# STM32WL_LHCbit.net
KiCad netlist of a schematic drawn in Altium Designer
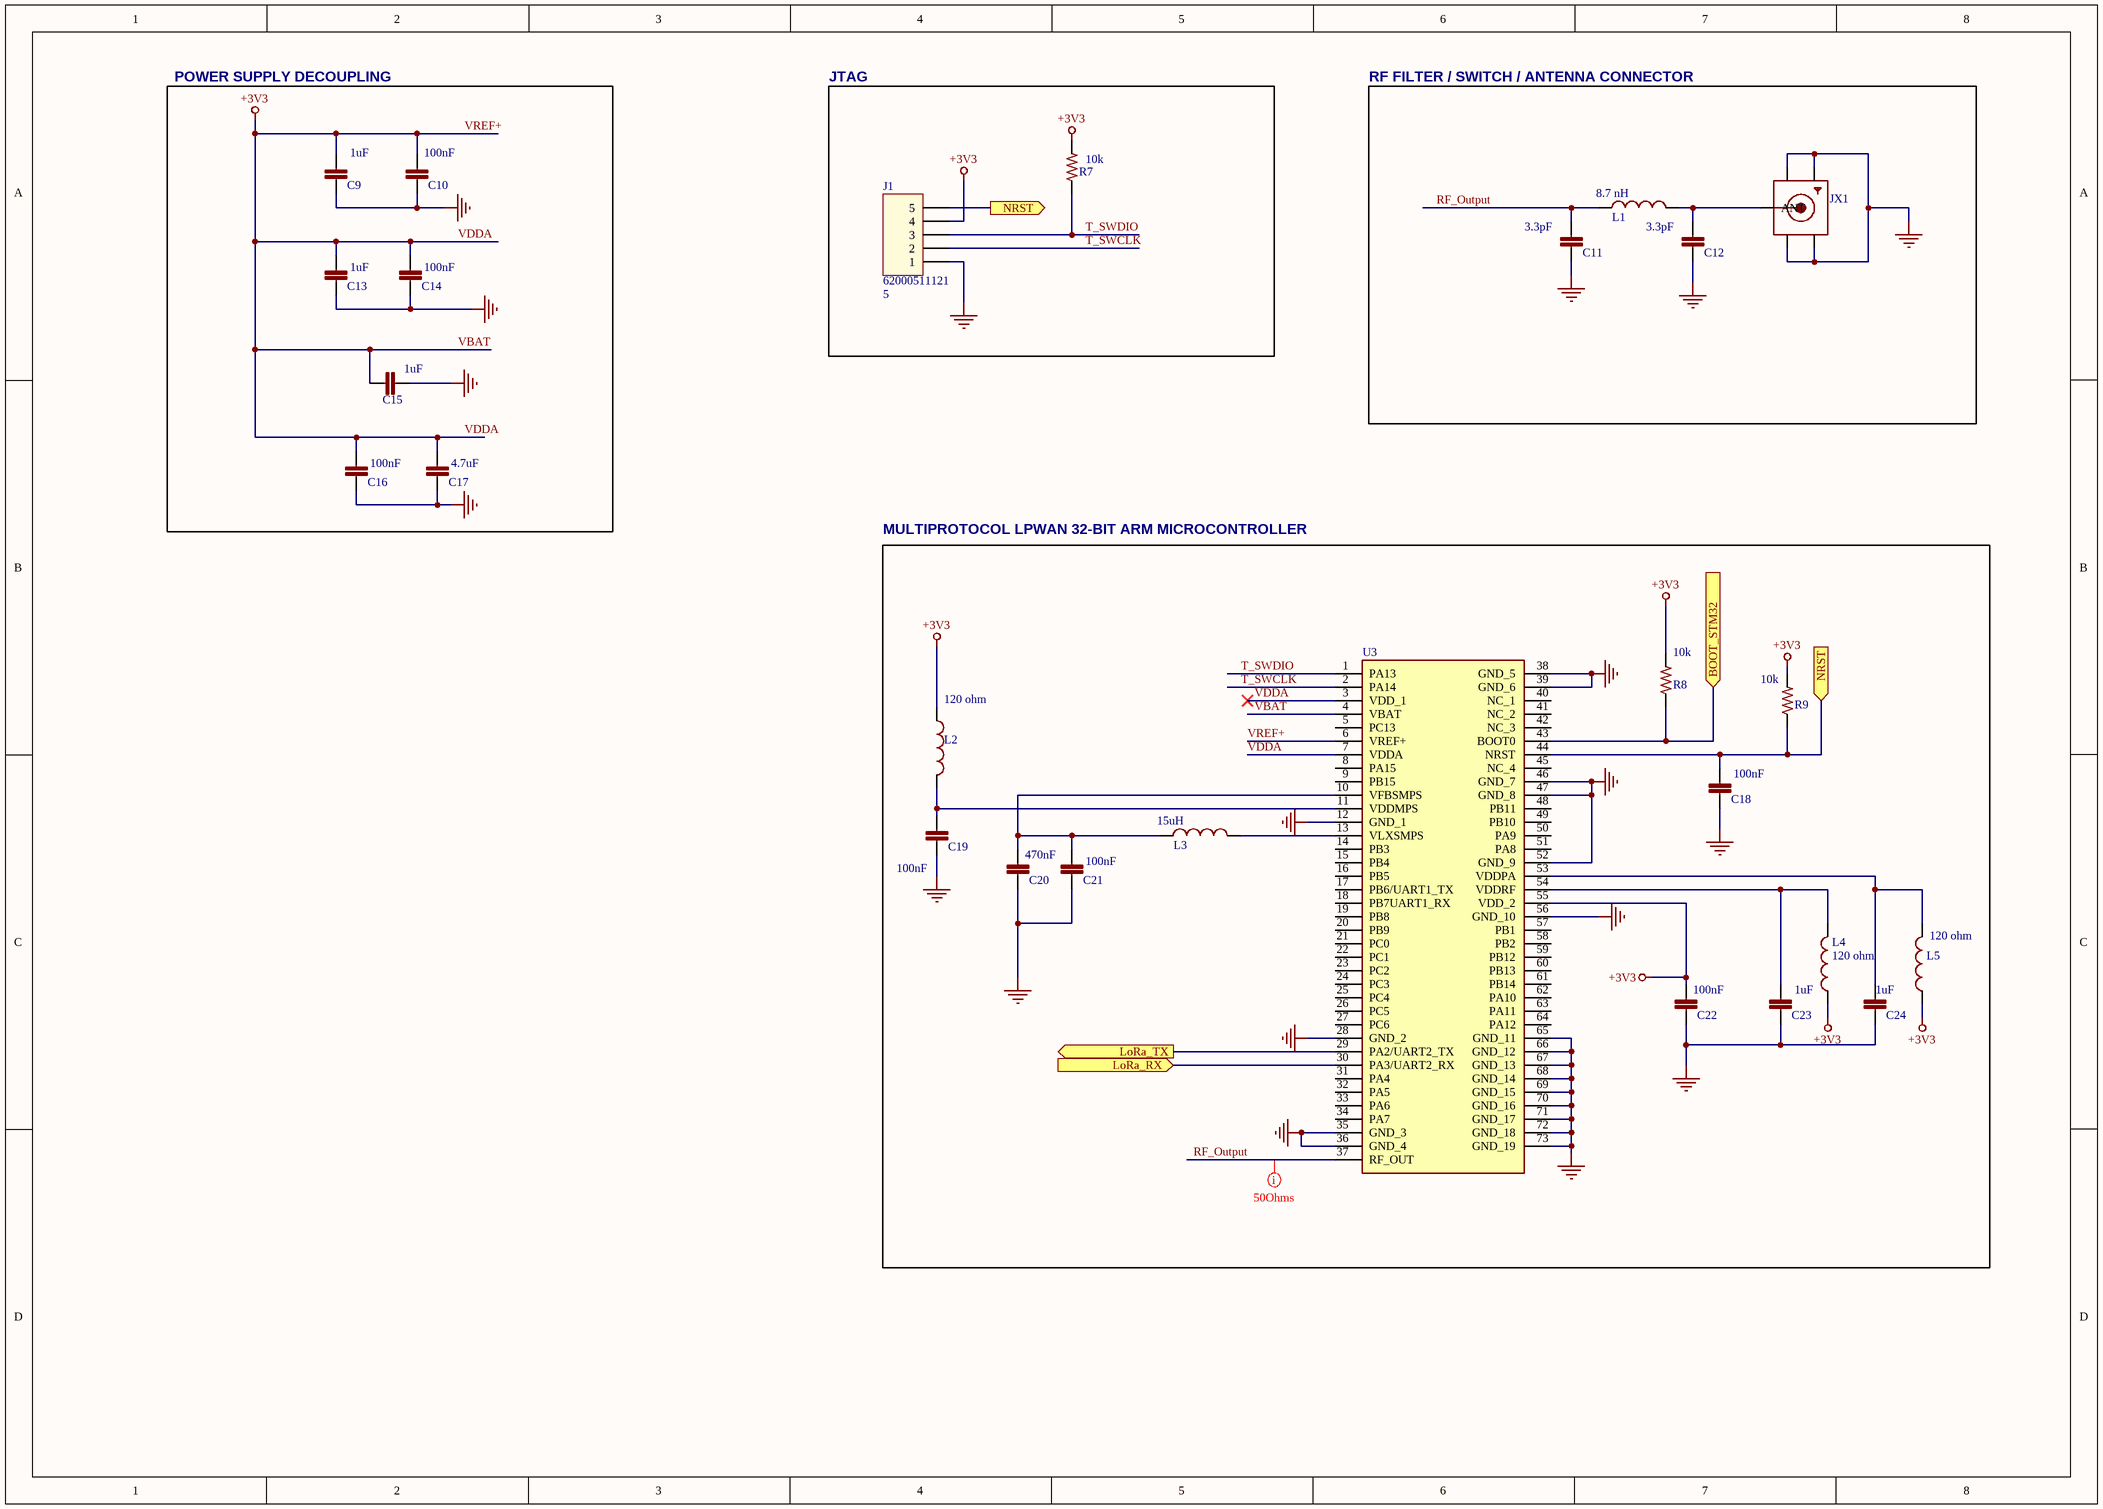
[diagram p0: STM32WL_LHCbit.SchDoc]

(export (version "E")
  (design (tool "Eeschema 10.0.6"))
  (components
    (comp (ref "C9")
      (value "1uF")
      (footprint "C0402")
      (fields (field (name "PART NUMBER") "CL05A105KA5NQNC") (field (name "Comment") "C-EUC0402"))
      (libsource (lib "") (part "C-EUC0402_1"))
    )
    (comp (ref "C10")
      (value "100nF")
      (footprint "C0402")
      (fields (field (name "PART NUMBER") "C0402C104K8") (field (name "Comment") "C-EUC0402"))
      (libsource (lib "") (part "C-EUC0402_1"))
    )
    (comp (ref "C11")
      (value "3.3pF")
      (footprint "C0402")
      (fields (field (name "PART NUMBER") "GRM1555C1H3R3WA01D") (field (name "Comment") "C-EUC0402"))
      (libsource (lib "rcl") (part "C-EUC0402"))
    )
    (comp (ref "C12")
      (value "3.3pF")
      (footprint "C0402")
      (fields (field (name "PART NUMBER") "GRM1555C1H3R3WA01D") (field (name "Comment") "C-EUC0402"))
      (libsource (lib "rcl") (part "C-EUC0402"))
    )
    (comp (ref "C13")
      (value "1uF")
      (footprint "C0402")
      (fields (field (name "PART NUMBER") "CL05A105KA5NQNC") (field (name "Comment") "C-EUC0402"))
      (libsource (lib "") (part "C-EUC0402_1"))
    )
    (comp (ref "C14")
      (value "100nF")
      (footprint "C0402")
      (fields (field (name "PART NUMBER") "C0402C104K8") (field (name "Comment") "C-EUC0402"))
      (libsource (lib "") (part "C-EUC0402_1"))
    )
    (comp (ref "C15")
      (value "1uF")
      (footprint "C0402")
      (fields (field (name "PART NUMBER") "CL05A105KA5NQNC") (field (name "Comment") "C-EUC0402"))
      (libsource (lib "") (part "C-EUC0402_2"))
    )
    (comp (ref "C16")
      (value "100nF")
      (footprint "C0402")
      (fields (field (name "PART NUMBER") "C0402C104K8") (field (name "Comment") "C-EUC0402"))
      (libsource (lib "") (part "C-EUC0402_1"))
    )
    (comp (ref "C17")
      (value "4.7uF")
      (footprint "C0402")
      (fields (field (name "PART NUMBER") "CL05A475MQ5NRNC") (field (name "Comment") "C-EUC0402"))
      (libsource (lib "") (part "C-EUC0402_1"))
    )
    (comp (ref "C18")
      (value "100nF")
      (footprint "C0402")
      (fields (field (name "PART NUMBER") "C0402C104K8") (field (name "Comment") "C-EUC0402"))
      (libsource (lib "") (part "C-EUC0402_1"))
    )
    (comp (ref "C19")
      (value "100nF")
      (footprint "C0402")
      (fields (field (name "PART NUMBER") "C0402C104K8") (field (name "Comment") "C-EUC0402"))
      (libsource (lib "") (part "C-EUC0402_1"))
    )
    (comp (ref "C20")
      (value "470nF")
      (footprint "C0402")
      (fields (field (name "PART NUMBER") "GRM155R61H474KE11D") (field (name "Comment") "C-EUC0402"))
      (libsource (lib "") (part "C-EUC0402_1"))
    )
    (comp (ref "C21")
      (value "100nF")
      (footprint "C0402")
      (fields (field (name "PART NUMBER") "C0402C104K8") (field (name "Comment") "C-EUC0402"))
      (libsource (lib "") (part "C-EUC0402_1"))
    )
    (comp (ref "C22")
      (value "100nF")
      (footprint "C0402")
      (fields (field (name "PART NUMBER") "C0402C104K8") (field (name "Comment") "C-EUC0402"))
      (libsource (lib "") (part "C-EUC0402_1"))
    )
    (comp (ref "C23")
      (value "1uF")
      (footprint "C0402")
      (fields (field (name "PART NUMBER") "CL05A105KA5NQNC") (field (name "Comment") "C-EUC0402"))
      (libsource (lib "") (part "C-EUC0402_1"))
    )
    (comp (ref "C24")
      (value "1uF")
      (footprint "C0402")
      (fields (field (name "PART NUMBER") "CL05A105KA5NQNC") (field (name "Comment") "C-EUC0402"))
      (libsource (lib "") (part "C-EUC0402_1"))
    )
    (comp (ref "J1")
      (value "62000511121")
      (footprint "62000511121")
      (description "WR-PHD 2.00 mm THT Pin Header, 6p")
      (fields (field (name "ALTIUM_VALUE") "5"))
      (libsource (lib "Male_header_200mm") (part "62000511121"))
    )
    (comp (ref "JX1")
      (value "SMACONNECTOR_EDGE_UFL")
      (footprint "SMA_EDGELAUNCH_UFL")
      (fields (field (name "PART NUMBER") "SMA-J-P-H-ST-EM1"))
      (libsource (lib "TE") (part "SMACONNECTOR_EDGE_UFL"))
    )
    (comp (ref "L1")
      (value "8.7 nH")
      (footprint "L0402 - rounded")
      (fields (field (name "PART NUMBER") "LQW15AN8N7G00D") (field (name "Comment") "Ferrite bead 0402"))
      (libsource (lib "rcl") (part "L-US0402"))
    )
    (comp (ref "L2")
      (value "120 ohm")
      (footprint "L0603")
      (fields (field (name "PART NUMBER") "YI160808U121-2R5T") (field (name "Comment") "Ferrite bead 0603"))
      (libsource (lib "rcl") (part "L-US0603"))
    )
    (comp (ref "L3")
      (value "15uH")
      (footprint "L0805")
      (fields (field (name "PART NUMBER") "MLZ2012M150WTD25"))
      (libsource (lib "rcl") (part "L-US0805"))
    )
    (comp (ref "L4")
      (value "120 ohm")
      (footprint "L0603")
      (fields (field (name "PART NUMBER") "YI160808U121-2R5T") (field (name "Comment") "Ferrite bead 0603"))
      (libsource (lib "rcl") (part "L-US0603"))
    )
    (comp (ref "L5")
      (value "120 ohm")
      (footprint "L0603")
      (fields (field (name "PART NUMBER") "YI160808U121-2R5T") (field (name "Comment") "Ferrite bead 0603"))
      (libsource (lib "rcl") (part "L-US0603"))
    )
    (comp (ref "R7")
      (value "10k")
      (footprint "R0402")
      (fields (field (name "PART NUMBER") "RC0402FR-0710KL") (field (name "Comment") "R-US_R0402"))
      (libsource (lib "rcl") (part "R-US_R0402"))
    )
    (comp (ref "R8")
      (value "10k")
      (footprint "R0402")
      (fields (field (name "PART NUMBER") "RC0402FR-0710KL") (field (name "Comment") "R-US_R0402"))
      (libsource (lib "rcl") (part "R-US_R0402"))
    )
    (comp (ref "R9")
      (value "10k")
      (footprint "R0402")
      (fields (field (name "PART NUMBER") "RC0402FR-0710KL") (field (name "Comment") "R-US_R0402"))
      (libsource (lib "rcl") (part "R-US_R0402"))
    )
    (comp (ref "U3")
      (value "RAK3172-SiP")
      (footprint "RAK3172SiP")
      (description "Integrated Circuit")
      (fields (field (name "PART NUMBER") "RAK3172-SIP-9-SM-NI"))
      (libsource (lib "TE") (part "RAK3172-SiP"))
    )
  )
  (nets
    (net (code "1") (name "+3V3") (class "Default")
      (node (ref "C10") (pin "1") (pinfunction "1_1") (pintype "passive"))
      (node (ref "C13") (pin "1") (pinfunction "1_1") (pintype "passive"))
      (node (ref "C14") (pin "1") (pinfunction "1_1") (pintype "passive"))
      (node (ref "C15") (pin "1") (pinfunction "1_1") (pintype "passive"))
      (node (ref "C16") (pin "1") (pinfunction "1_1") (pintype "passive"))
      (node (ref "C17") (pin "1") (pinfunction "1_1") (pintype "passive"))
      (node (ref "C22") (pin "1") (pinfunction "1_1") (pintype "passive"))
      (node (ref "C9") (pin "1") (pinfunction "1_1") (pintype "passive"))
      (node (ref "J1") (pin "4") (pinfunction "4_4") (pintype "passive"))
      (node (ref "L2") (pin "1") (pinfunction "1_1") (pintype "passive"))
      (node (ref "L4") (pin "1") (pinfunction "1_1") (pintype "passive"))
      (node (ref "L5") (pin "1") (pinfunction "1_1") (pintype "passive"))
      (node (ref "R7") (pin "2") (pinfunction "2_2") (pintype "passive"))
      (node (ref "R8") (pin "2") (pinfunction "2_2") (pintype "passive"))
      (node (ref "R9") (pin "2") (pinfunction "2_2") (pintype "passive"))
      (node (ref "U3") (pin "3") (pinfunction "VDD_1_3") (pintype "passive"))
      (node (ref "U3") (pin "4") (pinfunction "VBAT_4") (pintype "passive"))
      (node (ref "U3") (pin "55") (pinfunction "VDD_2_55") (pintype "passive"))
      (node (ref "U3") (pin "6") (pinfunction "VREF+_6") (pintype "passive"))
      (node (ref "U3") (pin "7") (pinfunction "VDDA_7") (pintype "passive"))
    )
    (net (code "2") (name "/BOOT_STM32") (class "Default")
      (node (ref "R8") (pin "1") (pinfunction "1_1") (pintype "passive"))
      (node (ref "U3") (pin "43") (pinfunction "BOOT0_43") (pintype "passive"))
    )
    (net (code "3") (name "/LoRa_RX") (class "Default")
      (node (ref "U3") (pin "30") (pinfunction "PA3/UART2_RX_30") (pintype "passive"))
    )
    (net (code "4") (name "/LoRa_TX") (class "Default")
      (node (ref "U3") (pin "29") (pinfunction "PA2/UART2_TX_29") (pintype "passive"))
    )
    (net (code "5") (name "/NRST") (class "Default")
      (node (ref "C18") (pin "1") (pinfunction "1_1") (pintype "passive"))
      (node (ref "J1") (pin "5") (pinfunction "5_5") (pintype "passive"))
      (node (ref "R9") (pin "1") (pinfunction "1_1") (pintype "passive"))
      (node (ref "U3") (pin "44") (pinfunction "NRST_44") (pintype "passive"))
    )
    (net (code "6") (name "/RF_Output") (class "Default")
      (node (ref "C11") (pin "2") (pinfunction "2_2") (pintype "passive"))
      (node (ref "L1") (pin "1") (pinfunction "1_1") (pintype "passive"))
      (node (ref "U3") (pin "37") (pinfunction "RF_OUT_37") (pintype "passive"))
    )
    (net (code "7") (name "/T_SWCLK") (class "Default")
      (node (ref "J1") (pin "2") (pinfunction "2_2") (pintype "passive"))
      (node (ref "U3") (pin "2") (pinfunction "PA14_2") (pintype "passive"))
    )
    (net (code "8") (name "/T_SWDIO") (class "Default")
      (node (ref "J1") (pin "3") (pinfunction "3_3") (pintype "passive"))
      (node (ref "R7") (pin "1") (pinfunction "1_1") (pintype "passive"))
      (node (ref "U3") (pin "1") (pinfunction "PA13_1") (pintype "passive"))
    )
    (net (code "9") (name "GND") (class "Default")
      (node (ref "C10") (pin "2") (pinfunction "2_2") (pintype "passive"))
      (node (ref "C11") (pin "1") (pinfunction "1_1") (pintype "passive"))
      (node (ref "C12") (pin "1") (pinfunction "1_1") (pintype "passive"))
      (node (ref "C13") (pin "2") (pinfunction "2_2") (pintype "passive"))
      (node (ref "C14") (pin "2") (pinfunction "2_2") (pintype "passive"))
      (node (ref "C15") (pin "2") (pinfunction "2_2") (pintype "passive"))
      (node (ref "C16") (pin "2") (pinfunction "2_2") (pintype "passive"))
      (node (ref "C17") (pin "2") (pinfunction "2_2") (pintype "passive"))
      (node (ref "C18") (pin "2") (pinfunction "2_2") (pintype "passive"))
      (node (ref "C19") (pin "2") (pinfunction "2_2") (pintype "passive"))
      (node (ref "C20") (pin "2") (pinfunction "2_2") (pintype "passive"))
      (node (ref "C21") (pin "2") (pinfunction "2_2") (pintype "passive"))
      (node (ref "C22") (pin "2") (pinfunction "2_2") (pintype "passive"))
      (node (ref "C23") (pin "2") (pinfunction "2_2") (pintype "passive"))
      (node (ref "C24") (pin "2") (pinfunction "2_2") (pintype "passive"))
      (node (ref "C9") (pin "2") (pinfunction "2_2") (pintype "passive"))
      (node (ref "J1") (pin "1") (pinfunction "1_1") (pintype "passive"))
      (node (ref "JX1") (pin "GND@1") (pinfunction "GND1_GND@1") (pintype "power_in"))
      (node (ref "JX1") (pin "GND@2") (pinfunction "GND2_GND@2") (pintype "power_in"))
      (node (ref "JX1") (pin "GND@3") (pinfunction "GND3_GND@3") (pintype "power_in"))
      (node (ref "JX1") (pin "GND@4") (pinfunction "GND4_GND@4") (pintype "power_in"))
      (node (ref "U3") (pin "12") (pinfunction "GND_1_12") (pintype "passive"))
      (node (ref "U3") (pin "28") (pinfunction "GND_2_28") (pintype "passive"))
      (node (ref "U3") (pin "35") (pinfunction "GND_3_35") (pintype "passive"))
      (node (ref "U3") (pin "36") (pinfunction "GND_4_36") (pintype "passive"))
      (node (ref "U3") (pin "38") (pinfunction "GND_5_38") (pintype "passive"))
      (node (ref "U3") (pin "39") (pinfunction "GND_6_39") (pintype "passive"))
      (node (ref "U3") (pin "46") (pinfunction "GND_7_46") (pintype "passive"))
      (node (ref "U3") (pin "47") (pinfunction "GND_8_47") (pintype "passive"))
      (node (ref "U3") (pin "52") (pinfunction "GND_9_52") (pintype "passive"))
      (node (ref "U3") (pin "56") (pinfunction "GND_10_56") (pintype "passive"))
      (node (ref "U3") (pin "65") (pinfunction "GND_11_65") (pintype "passive"))
      (node (ref "U3") (pin "66") (pinfunction "GND_12_66") (pintype "passive"))
      (node (ref "U3") (pin "67") (pinfunction "GND_13_67") (pintype "passive"))
      (node (ref "U3") (pin "68") (pinfunction "GND_14_68") (pintype "passive"))
      (node (ref "U3") (pin "69") (pinfunction "GND_15_69") (pintype "passive"))
      (node (ref "U3") (pin "70") (pinfunction "GND_16_70") (pintype "passive"))
      (node (ref "U3") (pin "71") (pinfunction "GND_17_71") (pintype "passive"))
      (node (ref "U3") (pin "72") (pinfunction "GND_18_72") (pintype "passive"))
      (node (ref "U3") (pin "73") (pinfunction "GND_19_73") (pintype "passive"))
    )
    (net (code "10") (name "Net-(JX1-ANT)") (class "Default")
      (node (ref "C12") (pin "2") (pinfunction "2_2") (pintype "passive"))
      (node (ref "JX1") (pin "P") (pinfunction "ANT_P") (pintype "passive"))
      (node (ref "L1") (pin "2") (pinfunction "2_2") (pintype "passive"))
    )
    (net (code "11") (name "Net-(U3-VDDMPS)") (class "Default")
      (node (ref "C19") (pin "1") (pinfunction "1_1") (pintype "passive"))
      (node (ref "L2") (pin "2") (pinfunction "2_2") (pintype "passive"))
      (node (ref "U3") (pin "11") (pinfunction "VDDMPS_11") (pintype "passive"))
    )
    (net (code "12") (name "Net-(U3-VDDPA)") (class "Default")
      (node (ref "C24") (pin "1") (pinfunction "1_1") (pintype "passive"))
      (node (ref "L5") (pin "2") (pinfunction "2_2") (pintype "passive"))
      (node (ref "U3") (pin "53") (pinfunction "VDDPA_53") (pintype "passive"))
    )
    (net (code "13") (name "Net-(U3-VDDRF)") (class "Default")
      (node (ref "C23") (pin "1") (pinfunction "1_1") (pintype "passive"))
      (node (ref "L4") (pin "2") (pinfunction "2_2") (pintype "passive"))
      (node (ref "U3") (pin "54") (pinfunction "VDDRF_54") (pintype "passive"))
    )
    (net (code "14") (name "Net-(U3-VFBSMPS)") (class "Default")
      (node (ref "C20") (pin "1") (pinfunction "1_1") (pintype "passive"))
      (node (ref "C21") (pin "1") (pinfunction "1_1") (pintype "passive"))
      (node (ref "L3") (pin "1") (pinfunction "1_1") (pintype "passive"))
      (node (ref "U3") (pin "10") (pinfunction "VFBSMPS_10") (pintype "passive"))
    )
    (net (code "15") (name "Net-(U3-VLXSMPS)") (class "Default")
      (node (ref "L3") (pin "2") (pinfunction "2_2") (pintype "passive"))
      (node (ref "U3") (pin "13") (pinfunction "VLXSMPS_13") (pintype "passive"))
    )
    (net (code "16") (name "unconnected-(U3-NC_1-Pad40)") (class "Default")
      (node (ref "U3") (pin "40") (pinfunction "NC_1_40") (pintype "passive"))
    )
    (net (code "17") (name "unconnected-(U3-NC_2-Pad41)") (class "Default")
      (node (ref "U3") (pin "41") (pinfunction "NC_2_41") (pintype "passive"))
    )
    (net (code "18") (name "unconnected-(U3-NC_3-Pad42)") (class "Default")
      (node (ref "U3") (pin "42") (pinfunction "NC_3_42") (pintype "passive"))
    )
    (net (code "19") (name "unconnected-(U3-NC_4-Pad45)") (class "Default")
      (node (ref "U3") (pin "45") (pinfunction "NC_4_45") (pintype "passive"))
    )
    (net (code "20") (name "unconnected-(U3-PA4-Pad31)") (class "Default")
      (node (ref "U3") (pin "31") (pinfunction "PA4_31") (pintype "passive"))
    )
    (net (code "21") (name "unconnected-(U3-PA5-Pad32)") (class "Default")
      (node (ref "U3") (pin "32") (pinfunction "PA5_32") (pintype "passive"))
    )
    (net (code "22") (name "unconnected-(U3-PA6-Pad33)") (class "Default")
      (node (ref "U3") (pin "33") (pinfunction "PA6_33") (pintype "passive"))
    )
    (net (code "23") (name "unconnected-(U3-PA7-Pad34)") (class "Default")
      (node (ref "U3") (pin "34") (pinfunction "PA7_34") (pintype "passive"))
    )
    (net (code "24") (name "unconnected-(U3-PA8-Pad51)") (class "Default")
      (node (ref "U3") (pin "51") (pinfunction "PA8_51") (pintype "passive"))
    )
    (net (code "25") (name "unconnected-(U3-PA9-Pad50)") (class "Default")
      (node (ref "U3") (pin "50") (pinfunction "PA9_50") (pintype "passive"))
    )
    (net (code "26") (name "unconnected-(U3-PA10-Pad62)") (class "Default")
      (node (ref "U3") (pin "62") (pinfunction "PA10_62") (pintype "passive"))
    )
    (net (code "27") (name "unconnected-(U3-PA11-Pad63)") (class "Default")
      (node (ref "U3") (pin "63") (pinfunction "PA11_63") (pintype "passive"))
    )
    (net (code "28") (name "unconnected-(U3-PA12-Pad64)") (class "Default")
      (node (ref "U3") (pin "64") (pinfunction "PA12_64") (pintype "passive"))
    )
    (net (code "29") (name "unconnected-(U3-PA15-Pad8)") (class "Default")
      (node (ref "U3") (pin "8") (pinfunction "PA15_8") (pintype "passive"))
    )
    (net (code "30") (name "unconnected-(U3-PB1-Pad57)") (class "Default")
      (node (ref "U3") (pin "57") (pinfunction "PB1_57") (pintype "passive"))
    )
    (net (code "31") (name "unconnected-(U3-PB2-Pad58)") (class "Default")
      (node (ref "U3") (pin "58") (pinfunction "PB2_58") (pintype "passive"))
    )
    (net (code "32") (name "unconnected-(U3-PB3-Pad14)") (class "Default")
      (node (ref "U3") (pin "14") (pinfunction "PB3_14") (pintype "passive"))
    )
    (net (code "33") (name "unconnected-(U3-PB4-Pad15)") (class "Default")
      (node (ref "U3") (pin "15") (pinfunction "PB4_15") (pintype "passive"))
    )
    (net (code "34") (name "unconnected-(U3-PB5-Pad16)") (class "Default")
      (node (ref "U3") (pin "16") (pinfunction "PB5_16") (pintype "passive"))
    )
    (net (code "35") (name "unconnected-(U3-PB6{slash}UART1_TX-Pad17)") (class "Default")
      (node (ref "U3") (pin "17") (pinfunction "PB6/UART1_TX_17") (pintype "passive"))
    )
    (net (code "36") (name "unconnected-(U3-PB7UART1_RX-Pad18)") (class "Default")
      (node (ref "U3") (pin "18") (pinfunction "PB7UART1_RX_18") (pintype "passive"))
    )
    (net (code "37") (name "unconnected-(U3-PB8-Pad19)") (class "Default")
      (node (ref "U3") (pin "19") (pinfunction "PB8_19") (pintype "passive"))
    )
    (net (code "38") (name "unconnected-(U3-PB9-Pad20)") (class "Default")
      (node (ref "U3") (pin "20") (pinfunction "PB9_20") (pintype "passive"))
    )
    (net (code "39") (name "unconnected-(U3-PB10-Pad49)") (class "Default")
      (node (ref "U3") (pin "49") (pinfunction "PB10_49") (pintype "passive"))
    )
    (net (code "40") (name "unconnected-(U3-PB11-Pad48)") (class "Default")
      (node (ref "U3") (pin "48") (pinfunction "PB11_48") (pintype "passive"))
    )
    (net (code "41") (name "unconnected-(U3-PB12-Pad59)") (class "Default")
      (node (ref "U3") (pin "59") (pinfunction "PB12_59") (pintype "passive"))
    )
    (net (code "42") (name "unconnected-(U3-PB13-Pad60)") (class "Default")
      (node (ref "U3") (pin "60") (pinfunction "PB13_60") (pintype "passive"))
    )
    (net (code "43") (name "unconnected-(U3-PB14-Pad61)") (class "Default")
      (node (ref "U3") (pin "61") (pinfunction "PB14_61") (pintype "passive"))
    )
    (net (code "44") (name "unconnected-(U3-PB15-Pad9)") (class "Default")
      (node (ref "U3") (pin "9") (pinfunction "PB15_9") (pintype "passive"))
    )
    (net (code "45") (name "unconnected-(U3-PC0-Pad21)") (class "Default")
      (node (ref "U3") (pin "21") (pinfunction "PC0_21") (pintype "passive"))
    )
    (net (code "46") (name "unconnected-(U3-PC1-Pad22)") (class "Default")
      (node (ref "U3") (pin "22") (pinfunction "PC1_22") (pintype "passive"))
    )
    (net (code "47") (name "unconnected-(U3-PC2-Pad23)") (class "Default")
      (node (ref "U3") (pin "23") (pinfunction "PC2_23") (pintype "passive"))
    )
    (net (code "48") (name "unconnected-(U3-PC3-Pad24)") (class "Default")
      (node (ref "U3") (pin "24") (pinfunction "PC3_24") (pintype "passive"))
    )
    (net (code "49") (name "unconnected-(U3-PC4-Pad25)") (class "Default")
      (node (ref "U3") (pin "25") (pinfunction "PC4_25") (pintype "passive"))
    )
    (net (code "50") (name "unconnected-(U3-PC5-Pad26)") (class "Default")
      (node (ref "U3") (pin "26") (pinfunction "PC5_26") (pintype "passive"))
    )
    (net (code "51") (name "unconnected-(U3-PC6-Pad27)") (class "Default")
      (node (ref "U3") (pin "27") (pinfunction "PC6_27") (pintype "passive"))
    )
    (net (code "52") (name "unconnected-(U3-PC13-Pad5)") (class "Default")
      (node (ref "U3") (pin "5") (pinfunction "PC13_5") (pintype "passive"))
    )
  )
)
